# Schematic.net
KiCad netlist of a schematic drawn in EasyEDA Pro
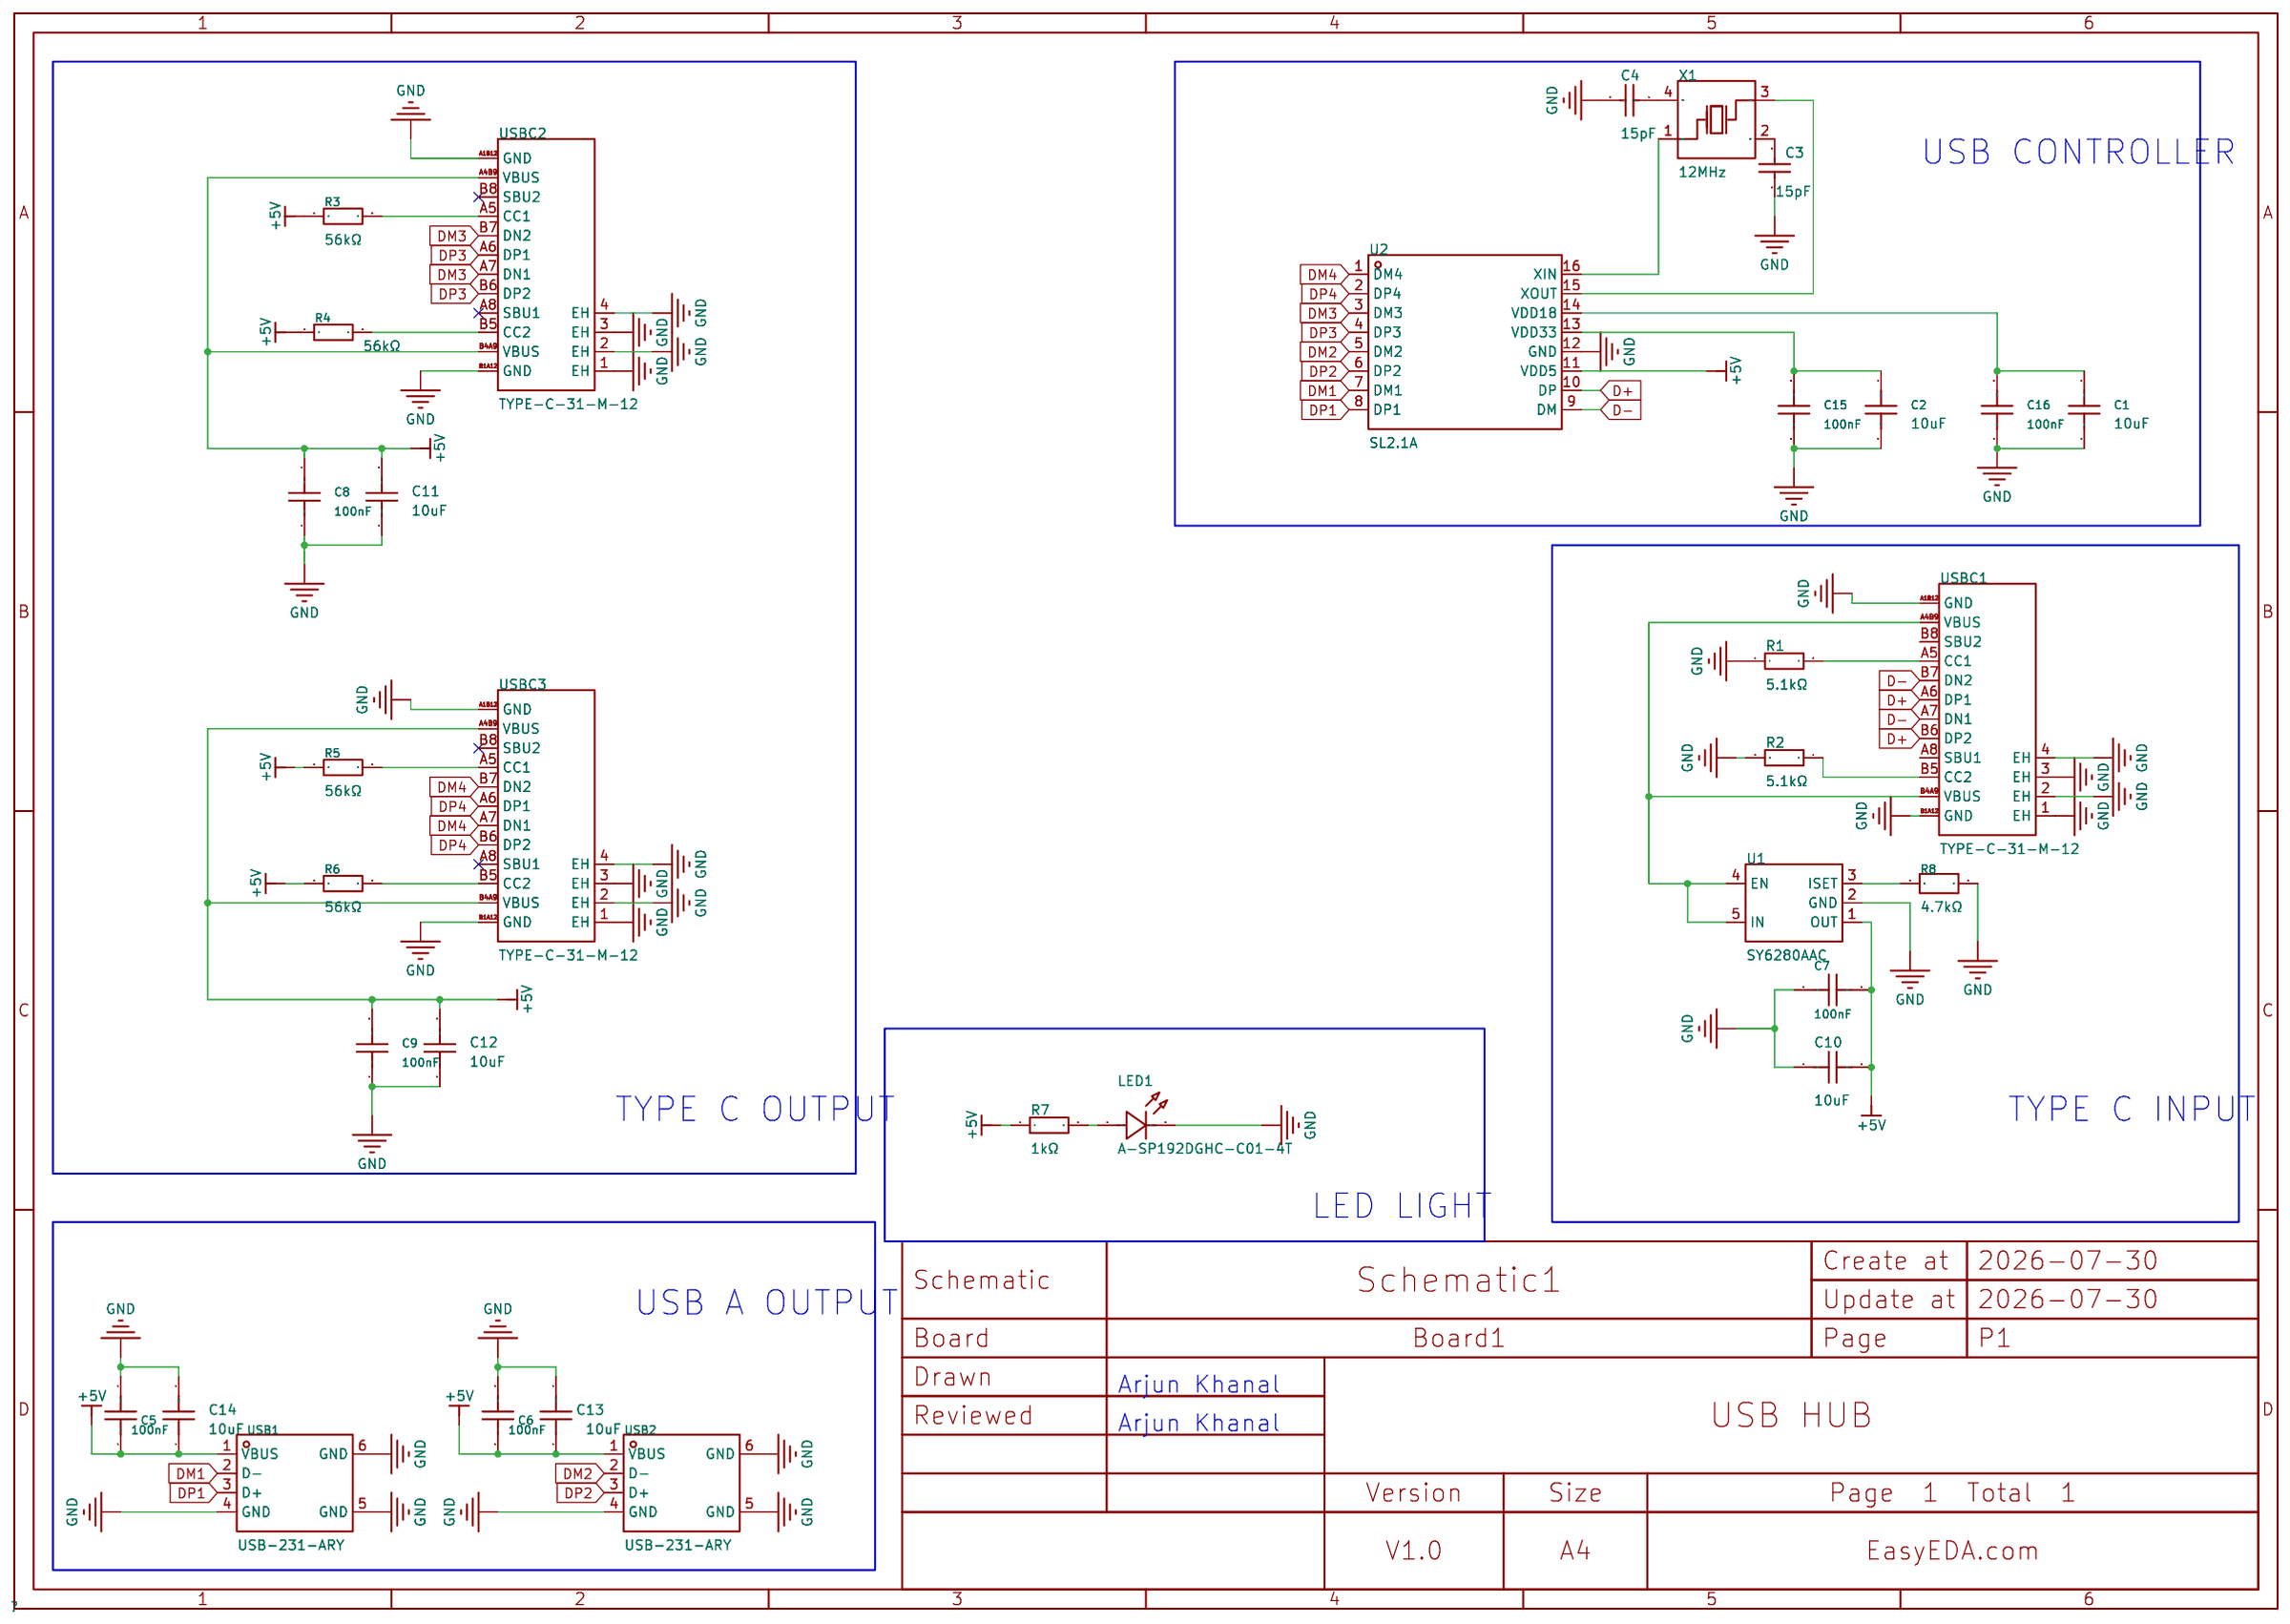
[diagram p0: schematic sheet]

(export (version "E")
  (design (tool "Eeschema 10.0.6"))
  (components
    (comp (ref "C1")
      (value "10uF")
      (footprint "easyedapro:C0603")
      (fields
        (field (name "Manufacturer Part") "CL10A106MA8NRNC")
        (field (name "Manufacturer") "SAMSUNG(三星)")
      )
      (libsource (lib "easyedapro") (part "CL10A106MA8NRNC"))
    )
    (comp (ref "C2")
      (value "10uF")
      (footprint "easyedapro:C0603")
      (fields
        (field (name "Manufacturer Part") "CL10A106MA8NRNC")
        (field (name "Manufacturer") "SAMSUNG(三星)")
      )
      (libsource (lib "easyedapro") (part "CL10A106MA8NRNC"))
    )
    (comp (ref "C3")
      (value "15pF")
      (footprint "easyedapro:C0603")
      (fields
        (field (name "Manufacturer Part") "CL10C150JB8NNNC")
        (field (name "Manufacturer") "SAMSUNG(三星)")
      )
      (libsource (lib "easyedapro") (part "CL10C150JB8NNNC"))
    )
    (comp (ref "C4")
      (value "15pF")
      (footprint "easyedapro:C0603")
      (fields
        (field (name "Manufacturer Part") "CL10C150JB8NNNC")
        (field (name "Manufacturer") "SAMSUNG(三星)")
      )
      (libsource (lib "easyedapro") (part "CL10C150JB8NNNC"))
    )
    (comp (ref "C5")
      (value "100nF")
      (footprint "easyedapro:C0603")
      (fields
        (field (name "Manufacturer Part") "CC0603KRX7R9BB104")
        (field (name "Manufacturer") "YAGEO(国巨)")
      )
      (libsource (lib "easyedapro") (part "CC0603KRX7R9BB104"))
    )
    (comp (ref "C6")
      (value "100nF")
      (footprint "easyedapro:C0603")
      (fields
        (field (name "Manufacturer Part") "CC0603KRX7R9BB104")
        (field (name "Manufacturer") "YAGEO(国巨)")
      )
      (libsource (lib "easyedapro") (part "CC0603KRX7R9BB104"))
    )
    (comp (ref "C7")
      (value "100nF")
      (footprint "easyedapro:C0603")
      (fields
        (field (name "Manufacturer Part") "CC0603KRX7R9BB104")
        (field (name "Manufacturer") "YAGEO(国巨)")
      )
      (libsource (lib "easyedapro") (part "CC0603KRX7R9BB104"))
    )
    (comp (ref "C8")
      (value "100nF")
      (footprint "easyedapro:C0603")
      (fields
        (field (name "Manufacturer Part") "CC0603KRX7R9BB104")
        (field (name "Manufacturer") "YAGEO(国巨)")
      )
      (libsource (lib "easyedapro") (part "CC0603KRX7R9BB104"))
    )
    (comp (ref "C9")
      (value "100nF")
      (footprint "easyedapro:C0603")
      (fields
        (field (name "Manufacturer Part") "CC0603KRX7R9BB104")
        (field (name "Manufacturer") "YAGEO(国巨)")
      )
      (libsource (lib "easyedapro") (part "CC0603KRX7R9BB104"))
    )
    (comp (ref "C10")
      (value "10uF")
      (footprint "easyedapro:C0805")
      (fields
        (field (name "Manufacturer Part") "CL21A106KAYNNNE")
        (field (name "Manufacturer") "SAMSUNG(三星)")
      )
      (libsource (lib "easyedapro") (part "CL21A106KAYNNNE"))
    )
    (comp (ref "C11")
      (value "10uF")
      (footprint "easyedapro:C0805")
      (fields
        (field (name "Manufacturer Part") "CL21A106KAYNNNE")
        (field (name "Manufacturer") "SAMSUNG(三星)")
      )
      (libsource (lib "easyedapro") (part "CL21A106KAYNNNE"))
    )
    (comp (ref "C12")
      (value "10uF")
      (footprint "easyedapro:C0805")
      (fields
        (field (name "Manufacturer Part") "CL21A106KAYNNNE")
        (field (name "Manufacturer") "SAMSUNG(三星)")
      )
      (libsource (lib "easyedapro") (part "CL21A106KAYNNNE"))
    )
    (comp (ref "C13")
      (value "10uF")
      (footprint "easyedapro:C0805")
      (fields
        (field (name "Manufacturer Part") "CL21A106KAYNNNE")
        (field (name "Manufacturer") "SAMSUNG(三星)")
      )
      (libsource (lib "easyedapro") (part "CL21A106KAYNNNE"))
    )
    (comp (ref "C14")
      (value "10uF")
      (footprint "easyedapro:C0805")
      (fields
        (field (name "Manufacturer Part") "CL21A106KAYNNNE")
        (field (name "Manufacturer") "SAMSUNG(三星)")
      )
      (libsource (lib "easyedapro") (part "CL21A106KAYNNNE"))
    )
    (comp (ref "C15")
      (value "100nF")
      (footprint "easyedapro:C0603")
      (fields
        (field (name "Manufacturer Part") "CC0603KRX7R9BB104")
        (field (name "Manufacturer") "YAGEO(国巨)")
      )
      (libsource (lib "easyedapro") (part "CC0603KRX7R9BB104"))
    )
    (comp (ref "C16")
      (value "100nF")
      (footprint "easyedapro:C0603")
      (fields
        (field (name "Manufacturer Part") "CC0603KRX7R9BB104")
        (field (name "Manufacturer") "YAGEO(国巨)")
      )
      (libsource (lib "easyedapro") (part "CC0603KRX7R9BB104"))
    )
    (comp (ref "LED1")
      (value "A-SP192DGHC-C01-4T")
      (footprint "easyedapro:LED0603-FD")
      (fields (field (name "Manufacturer") "Amicc(欧密格光电)"))
      (libsource (lib "easyedapro") (part "A-SP192DGHC-C01-4T"))
    )
    (comp (ref "R1")
      (value "5.1kΩ")
      (footprint "easyedapro:R0603")
      (fields
        (field (name "Manufacturer Part") "0603WAF5101T5E")
        (field (name "Manufacturer") "UNI-ROYAL(厚声)")
      )
      (libsource (lib "easyedapro") (part "0603WAF5101T5E"))
    )
    (comp (ref "R2")
      (value "5.1kΩ")
      (footprint "easyedapro:R0603")
      (fields
        (field (name "Manufacturer Part") "0603WAF5101T5E")
        (field (name "Manufacturer") "UNI-ROYAL(厚声)")
      )
      (libsource (lib "easyedapro") (part "0603WAF5101T5E"))
    )
    (comp (ref "R3")
      (value "56kΩ")
      (footprint "easyedapro:R0603")
      (fields
        (field (name "Manufacturer Part") "0603WAF5602T5E")
        (field (name "Manufacturer") "UNI-ROYAL(厚声)")
      )
      (libsource (lib "easyedapro") (part "0603WAF5602T5E"))
    )
    (comp (ref "R4")
      (value "56kΩ")
      (footprint "easyedapro:R0603")
      (fields
        (field (name "Manufacturer Part") "0603WAF5602T5E")
        (field (name "Manufacturer") "UNI-ROYAL(厚声)")
      )
      (libsource (lib "easyedapro") (part "0603WAF5602T5E"))
    )
    (comp (ref "R5")
      (value "56kΩ")
      (footprint "easyedapro:R0603")
      (fields
        (field (name "Manufacturer Part") "0603WAF5602T5E")
        (field (name "Manufacturer") "UNI-ROYAL(厚声)")
      )
      (libsource (lib "easyedapro") (part "0603WAF5602T5E"))
    )
    (comp (ref "R6")
      (value "56kΩ")
      (footprint "easyedapro:R0603")
      (fields
        (field (name "Manufacturer Part") "0603WAF5602T5E")
        (field (name "Manufacturer") "UNI-ROYAL(厚声)")
      )
      (libsource (lib "easyedapro") (part "0603WAF5602T5E"))
    )
    (comp (ref "R7")
      (value "1kΩ")
      (footprint "easyedapro:R0805")
      (fields (field (name "Manufacturer Part") "RC0805FR-071KL") (field (name "Manufacturer") "YAGEO(国巨)"))
      (libsource (lib "easyedapro") (part "RC0805FR-071KL"))
    )
    (comp (ref "R8")
      (value "4.7kΩ")
      (footprint "easyedapro:R0603")
      (fields
        (field (name "Manufacturer Part") "HoLTT0603-1/10W-4.7K-1%")
        (field (name "Manufacturer") "Milliohm(毫欧)")
      )
      (libsource (lib "easyedapro") (part "HOLTT0603-1/10W-4.7K-1%"))
    )
    (comp (ref "U1")
      (value "SY6280AAC")
      (footprint "easyedapro:SOT-23-5_L3.0-W1.7-P0.95-LS2.8-BL")
      (fields (field (name "Manufacturer") "Silergy(矽力杰)"))
      (libsource (lib "easyedapro") (part "SY6280AAC"))
    )
    (comp (ref "U2")
      (value "SL2.1A")
      (footprint "easyedapro:SOP-16_L10.0-W3.9-P1.27-LS6.0-BL")
      (fields (field (name "Manufacturer") "CoreChips(和芯润德)"))
      (libsource (lib "easyedapro") (part "SL2.1A"))
    )
    (comp (ref "USB1")
      (value "USB-231-ARY")
      (footprint "easyedapro:USB-A-TH_USB-231-ARY")
      (fields (field (name "Manufacturer") "XUNPU(讯普)"))
      (libsource (lib "easyedapro") (part "USB-231-ARY"))
    )
    (comp (ref "USB2")
      (value "USB-231-ARY")
      (footprint "easyedapro:USB-A-TH_USB-231-ARY")
      (fields (field (name "Manufacturer") "XUNPU(讯普)"))
      (libsource (lib "easyedapro") (part "USB-231-ARY"))
    )
    (comp (ref "USBC1")
      (value "TYPE-C-31-M-12")
      (footprint "easyedapro:USB-C_SMD-TYPE-C-31-M-12_1")
      (fields (field (name "Manufacturer") "韩国韩荣"))
      (libsource (lib "easyedapro") (part "TYPE-C-31-M-12"))
    )
    (comp (ref "USBC2")
      (value "TYPE-C-31-M-12")
      (footprint "easyedapro:USB-C_SMD-TYPE-C-31-M-12_1")
      (fields (field (name "Manufacturer") "韩国韩荣"))
      (libsource (lib "easyedapro") (part "TYPE-C-31-M-12"))
    )
    (comp (ref "USBC3")
      (value "TYPE-C-31-M-12")
      (footprint "easyedapro:USB-C_SMD-TYPE-C-31-M-12_1")
      (fields (field (name "Manufacturer") "韩国韩荣"))
      (libsource (lib "easyedapro") (part "TYPE-C-31-M-12"))
    )
    (comp (ref "X1")
      (value "12MHz")
      (footprint "easyedapro:CRYSTAL-SMD_4P-L3.2-W2.5-BL")
      (fields (field (name "Manufacturer Part") "X322512MSB4SI") (field (name "Manufacturer") "YXC(扬兴晶振)"))
      (libsource (lib "easyedapro") (part "X322512MSB4SI"))
    )
  )
  (nets
    (net (code "1") (name "+5V") (class "Default")
      (node (ref "C10") (pin "2") (pinfunction "2_2") (pintype "unspecified"))
      (node (ref "C11") (pin "2") (pinfunction "2_2") (pintype "unspecified"))
      (node (ref "C12") (pin "2") (pinfunction "2_2") (pintype "unspecified"))
      (node (ref "C13") (pin "1") (pinfunction "1_1") (pintype "unspecified"))
      (node (ref "C14") (pin "1") (pinfunction "1_1") (pintype "unspecified"))
      (node (ref "C5") (pin "1") (pinfunction "1_1") (pintype "unspecified"))
      (node (ref "C6") (pin "1") (pinfunction "1_1") (pintype "unspecified"))
      (node (ref "C7") (pin "2") (pinfunction "2_2") (pintype "unspecified"))
      (node (ref "C8") (pin "2") (pinfunction "2_2") (pintype "unspecified"))
      (node (ref "C9") (pin "2") (pinfunction "2_2") (pintype "unspecified"))
      (node (ref "R3") (pin "1") (pinfunction "1_1") (pintype "input"))
      (node (ref "R4") (pin "1") (pinfunction "1_1") (pintype "input"))
      (node (ref "R5") (pin "1") (pinfunction "1_1") (pintype "input"))
      (node (ref "R6") (pin "1") (pinfunction "1_1") (pintype "input"))
      (node (ref "R7") (pin "1") (pinfunction "1_1") (pintype "input"))
      (node (ref "U1") (pin "1") (pinfunction "OUT_1") (pintype "unspecified"))
      (node (ref "U2") (pin "11") (pinfunction "VDD5_11") (pintype "unspecified"))
      (node (ref "USB1") (pin "1") (pinfunction "VBUS_1") (pintype "input"))
      (node (ref "USB2") (pin "1") (pinfunction "VBUS_1") (pintype "input"))
      (node (ref "USBC2") (pin "A4B9") (pinfunction "VBUS_A4B9") (pintype "unspecified"))
      (node (ref "USBC2") (pin "B4A9") (pinfunction "VBUS_B4A9") (pintype "unspecified"))
      (node (ref "USBC3") (pin "A4B9") (pinfunction "VBUS_A4B9") (pintype "unspecified"))
      (node (ref "USBC3") (pin "B4A9") (pinfunction "VBUS_B4A9") (pintype "unspecified"))
    )
    (net (code "2") (name "D+") (class "Default")
      (node (ref "U2") (pin "10") (pinfunction "DP_10") (pintype "unspecified"))
      (node (ref "USBC1") (pin "A6") (pinfunction "DP1_A6") (pintype "unspecified"))
      (node (ref "USBC1") (pin "B6") (pinfunction "DP2_B6") (pintype "unspecified"))
    )
    (net (code "3") (name "D-") (class "Default")
      (node (ref "U2") (pin "9") (pinfunction "DM_9") (pintype "unspecified"))
      (node (ref "USBC1") (pin "A7") (pinfunction "DN1_A7") (pintype "unspecified"))
      (node (ref "USBC1") (pin "B7") (pinfunction "DN2_B7") (pintype "unspecified"))
    )
    (net (code "4") (name "DM1") (class "Default")
      (node (ref "U2") (pin "7") (pinfunction "DM1_7") (pintype "unspecified"))
      (node (ref "USB1") (pin "2") (pinfunction "D-_2") (pintype "input"))
    )
    (net (code "5") (name "DM2") (class "Default")
      (node (ref "U2") (pin "5") (pinfunction "DM2_5") (pintype "unspecified"))
      (node (ref "USB2") (pin "2") (pinfunction "D-_2") (pintype "input"))
    )
    (net (code "6") (name "DM3") (class "Default")
      (node (ref "U2") (pin "3") (pinfunction "DM3_3") (pintype "unspecified"))
      (node (ref "USBC2") (pin "A7") (pinfunction "DN1_A7") (pintype "unspecified"))
      (node (ref "USBC2") (pin "B7") (pinfunction "DN2_B7") (pintype "unspecified"))
    )
    (net (code "7") (name "DM4") (class "Default")
      (node (ref "U2") (pin "1") (pinfunction "DM4_1") (pintype "unspecified"))
      (node (ref "USBC3") (pin "A7") (pinfunction "DN1_A7") (pintype "unspecified"))
      (node (ref "USBC3") (pin "B7") (pinfunction "DN2_B7") (pintype "unspecified"))
    )
    (net (code "8") (name "DP1") (class "Default")
      (node (ref "U2") (pin "8") (pinfunction "DP1_8") (pintype "unspecified"))
      (node (ref "USB1") (pin "3") (pinfunction "D+_3") (pintype "input"))
    )
    (net (code "9") (name "DP2") (class "Default")
      (node (ref "U2") (pin "6") (pinfunction "DP2_6") (pintype "unspecified"))
      (node (ref "USB2") (pin "3") (pinfunction "D+_3") (pintype "input"))
    )
    (net (code "10") (name "DP3") (class "Default")
      (node (ref "U2") (pin "4") (pinfunction "DP3_4") (pintype "unspecified"))
      (node (ref "USBC2") (pin "A6") (pinfunction "DP1_A6") (pintype "unspecified"))
      (node (ref "USBC2") (pin "B6") (pinfunction "DP2_B6") (pintype "unspecified"))
    )
    (net (code "11") (name "DP4") (class "Default")
      (node (ref "U2") (pin "2") (pinfunction "DP4_2") (pintype "unspecified"))
      (node (ref "USBC3") (pin "A6") (pinfunction "DP1_A6") (pintype "unspecified"))
      (node (ref "USBC3") (pin "B6") (pinfunction "DP2_B6") (pintype "unspecified"))
    )
    (net (code "12") (name "GND") (class "Default")
      (node (ref "C1") (pin "2") (pinfunction "2_2") (pintype "input"))
      (node (ref "C10") (pin "1") (pinfunction "1_1") (pintype "unspecified"))
      (node (ref "C11") (pin "1") (pinfunction "1_1") (pintype "unspecified"))
      (node (ref "C12") (pin "1") (pinfunction "1_1") (pintype "unspecified"))
      (node (ref "C13") (pin "2") (pinfunction "2_2") (pintype "unspecified"))
      (node (ref "C14") (pin "2") (pinfunction "2_2") (pintype "unspecified"))
      (node (ref "C15") (pin "1") (pinfunction "1_1") (pintype "unspecified"))
      (node (ref "C16") (pin "1") (pinfunction "1_1") (pintype "unspecified"))
      (node (ref "C2") (pin "2") (pinfunction "2_2") (pintype "input"))
      (node (ref "C3") (pin "1") (pinfunction "1_1") (pintype "input"))
      (node (ref "C4") (pin "2") (pinfunction "2_2") (pintype "input"))
      (node (ref "C5") (pin "2") (pinfunction "2_2") (pintype "unspecified"))
      (node (ref "C6") (pin "2") (pinfunction "2_2") (pintype "unspecified"))
      (node (ref "C7") (pin "1") (pinfunction "1_1") (pintype "unspecified"))
      (node (ref "C8") (pin "1") (pinfunction "1_1") (pintype "unspecified"))
      (node (ref "C9") (pin "1") (pinfunction "1_1") (pintype "unspecified"))
      (node (ref "LED1") (pin "2") (pinfunction "K_2") (pintype "unspecified"))
      (node (ref "R1") (pin "1") (pinfunction "1_1") (pintype "input"))
      (node (ref "R2") (pin "2") (pinfunction "2_2") (pintype "input"))
      (node (ref "R8") (pin "2") (pinfunction "2_2") (pintype "input"))
      (node (ref "U1") (pin "2") (pinfunction "GND_2") (pintype "unspecified"))
      (node (ref "U2") (pin "12") (pinfunction "GND_12") (pintype "unspecified"))
      (node (ref "USB1") (pin "4") (pinfunction "GND_4") (pintype "input"))
      (node (ref "USB1") (pin "5") (pinfunction "GND_5") (pintype "input"))
      (node (ref "USB1") (pin "6") (pinfunction "GND_6") (pintype "input"))
      (node (ref "USB2") (pin "4") (pinfunction "GND_4") (pintype "input"))
      (node (ref "USB2") (pin "5") (pinfunction "GND_5") (pintype "input"))
      (node (ref "USB2") (pin "6") (pinfunction "GND_6") (pintype "input"))
      (node (ref "USBC1") (pin "1") (pinfunction "EH_1") (pintype "unspecified"))
      (node (ref "USBC1") (pin "2") (pinfunction "EH_2") (pintype "unspecified"))
      (node (ref "USBC1") (pin "3") (pinfunction "EH_3") (pintype "unspecified"))
      (node (ref "USBC1") (pin "4") (pinfunction "EH_4") (pintype "unspecified"))
      (node (ref "USBC1") (pin "A1B12") (pinfunction "GND_A1B12") (pintype "unspecified"))
      (node (ref "USBC1") (pin "B1A12") (pinfunction "GND_B1A12") (pintype "unspecified"))
      (node (ref "USBC2") (pin "1") (pinfunction "EH_1") (pintype "unspecified"))
      (node (ref "USBC2") (pin "2") (pinfunction "EH_2") (pintype "unspecified"))
      (node (ref "USBC2") (pin "3") (pinfunction "EH_3") (pintype "unspecified"))
      (node (ref "USBC2") (pin "4") (pinfunction "EH_4") (pintype "unspecified"))
      (node (ref "USBC2") (pin "A1B12") (pinfunction "GND_A1B12") (pintype "unspecified"))
      (node (ref "USBC2") (pin "B1A12") (pinfunction "GND_B1A12") (pintype "unspecified"))
      (node (ref "USBC3") (pin "1") (pinfunction "EH_1") (pintype "unspecified"))
      (node (ref "USBC3") (pin "2") (pinfunction "EH_2") (pintype "unspecified"))
      (node (ref "USBC3") (pin "3") (pinfunction "EH_3") (pintype "unspecified"))
      (node (ref "USBC3") (pin "4") (pinfunction "EH_4") (pintype "unspecified"))
      (node (ref "USBC3") (pin "A1B12") (pinfunction "GND_A1B12") (pintype "unspecified"))
      (node (ref "USBC3") (pin "B1A12") (pinfunction "GND_B1A12") (pintype "unspecified"))
    )
    (net (code "13") (name "Net-(C3-Pad2)") (class "Default")
      (node (ref "C3") (pin "2") (pinfunction "2_2") (pintype "input"))
      (node (ref "X1") (pin "2") (pinfunction "GND_2") (pintype "unspecified"))
    )
    (net (code "14") (name "Net-(C4-Pad1)") (class "Default")
      (node (ref "C4") (pin "1") (pinfunction "1_1") (pintype "input"))
      (node (ref "X1") (pin "4") (pinfunction "GND_4") (pintype "unspecified"))
    )
    (net (code "15") (name "Net-(LED1-A)") (class "Default")
      (node (ref "LED1") (pin "1") (pinfunction "A_1") (pintype "unspecified"))
      (node (ref "R7") (pin "2") (pinfunction "2_2") (pintype "input"))
    )
    (net (code "16") (name "Net-(U1-EN)") (class "Default")
      (node (ref "U1") (pin "4") (pinfunction "EN_4") (pintype "unspecified"))
      (node (ref "U1") (pin "5") (pinfunction "IN_5") (pintype "unspecified"))
      (node (ref "USBC1") (pin "A4B9") (pinfunction "VBUS_A4B9") (pintype "unspecified"))
      (node (ref "USBC1") (pin "B4A9") (pinfunction "VBUS_B4A9") (pintype "unspecified"))
    )
    (net (code "17") (name "Net-(U1-ISET)") (class "Default")
      (node (ref "R8") (pin "1") (pinfunction "1_1") (pintype "input"))
      (node (ref "U1") (pin "3") (pinfunction "ISET_3") (pintype "unspecified"))
    )
    (net (code "18") (name "Net-(U2-VDD18)") (class "Default")
      (node (ref "C1") (pin "1") (pinfunction "1_1") (pintype "input"))
      (node (ref "C16") (pin "2") (pinfunction "2_2") (pintype "unspecified"))
      (node (ref "U2") (pin "14") (pinfunction "VDD18_14") (pintype "unspecified"))
    )
    (net (code "19") (name "Net-(U2-VDD33)") (class "Default")
      (node (ref "C15") (pin "2") (pinfunction "2_2") (pintype "unspecified"))
      (node (ref "C2") (pin "1") (pinfunction "1_1") (pintype "input"))
      (node (ref "U2") (pin "13") (pinfunction "VDD33_13") (pintype "unspecified"))
    )
    (net (code "20") (name "Net-(U2-XIN)") (class "Default")
      (node (ref "U2") (pin "16") (pinfunction "XIN_16") (pintype "unspecified"))
      (node (ref "X1") (pin "1") (pinfunction "OSC1_1") (pintype "unspecified"))
    )
    (net (code "21") (name "Net-(U2-XOUT)") (class "Default")
      (node (ref "U2") (pin "15") (pinfunction "XOUT_15") (pintype "unspecified"))
      (node (ref "X1") (pin "3") (pinfunction "OSC2_3") (pintype "unspecified"))
    )
    (net (code "22") (name "Net-(USBC1-CC1)") (class "Default")
      (node (ref "R1") (pin "2") (pinfunction "2_2") (pintype "input"))
      (node (ref "USBC1") (pin "A5") (pinfunction "CC1_A5") (pintype "unspecified"))
    )
    (net (code "23") (name "Net-(USBC1-CC2)") (class "Default")
      (node (ref "R2") (pin "1") (pinfunction "1_1") (pintype "input"))
      (node (ref "USBC1") (pin "B5") (pinfunction "CC2_B5") (pintype "unspecified"))
    )
    (net (code "24") (name "Net-(USBC2-CC1)") (class "Default")
      (node (ref "R3") (pin "2") (pinfunction "2_2") (pintype "input"))
      (node (ref "USBC2") (pin "A5") (pinfunction "CC1_A5") (pintype "unspecified"))
    )
    (net (code "25") (name "Net-(USBC2-CC2)") (class "Default")
      (node (ref "R4") (pin "2") (pinfunction "2_2") (pintype "input"))
      (node (ref "USBC2") (pin "B5") (pinfunction "CC2_B5") (pintype "unspecified"))
    )
    (net (code "26") (name "Net-(USBC3-CC1)") (class "Default")
      (node (ref "R5") (pin "2") (pinfunction "2_2") (pintype "input"))
      (node (ref "USBC3") (pin "A5") (pinfunction "CC1_A5") (pintype "unspecified"))
    )
    (net (code "27") (name "Net-(USBC3-CC2)") (class "Default")
      (node (ref "R6") (pin "2") (pinfunction "2_2") (pintype "input"))
      (node (ref "USBC3") (pin "B5") (pinfunction "CC2_B5") (pintype "unspecified"))
    )
    (net (code "28") (name "unconnected-(USBC1-SBU1-PadA8)") (class "Default")
      (node (ref "USBC1") (pin "A8") (pinfunction "SBU1_A8") (pintype "unspecified"))
    )
    (net (code "29") (name "unconnected-(USBC1-SBU2-PadB8)") (class "Default")
      (node (ref "USBC1") (pin "B8") (pinfunction "SBU2_B8") (pintype "unspecified"))
    )
    (net (code "30") (name "unconnected-(USBC2-SBU1-PadA8)") (class "Default")
      (node (ref "USBC2") (pin "A8") (pinfunction "SBU1_A8") (pintype "unspecified+no_connect"))
    )
    (net (code "31") (name "unconnected-(USBC2-SBU2-PadB8)") (class "Default")
      (node (ref "USBC2") (pin "B8") (pinfunction "SBU2_B8") (pintype "unspecified+no_connect"))
    )
    (net (code "32") (name "unconnected-(USBC3-SBU1-PadA8)") (class "Default")
      (node (ref "USBC3") (pin "A8") (pinfunction "SBU1_A8") (pintype "unspecified+no_connect"))
    )
    (net (code "33") (name "unconnected-(USBC3-SBU2-PadB8)") (class "Default")
      (node (ref "USBC3") (pin "B8") (pinfunction "SBU2_B8") (pintype "unspecified+no_connect"))
    )
  )
)
